# GWLSensorv1.net
KiCad netlist of a schematic drawn in EAGLE
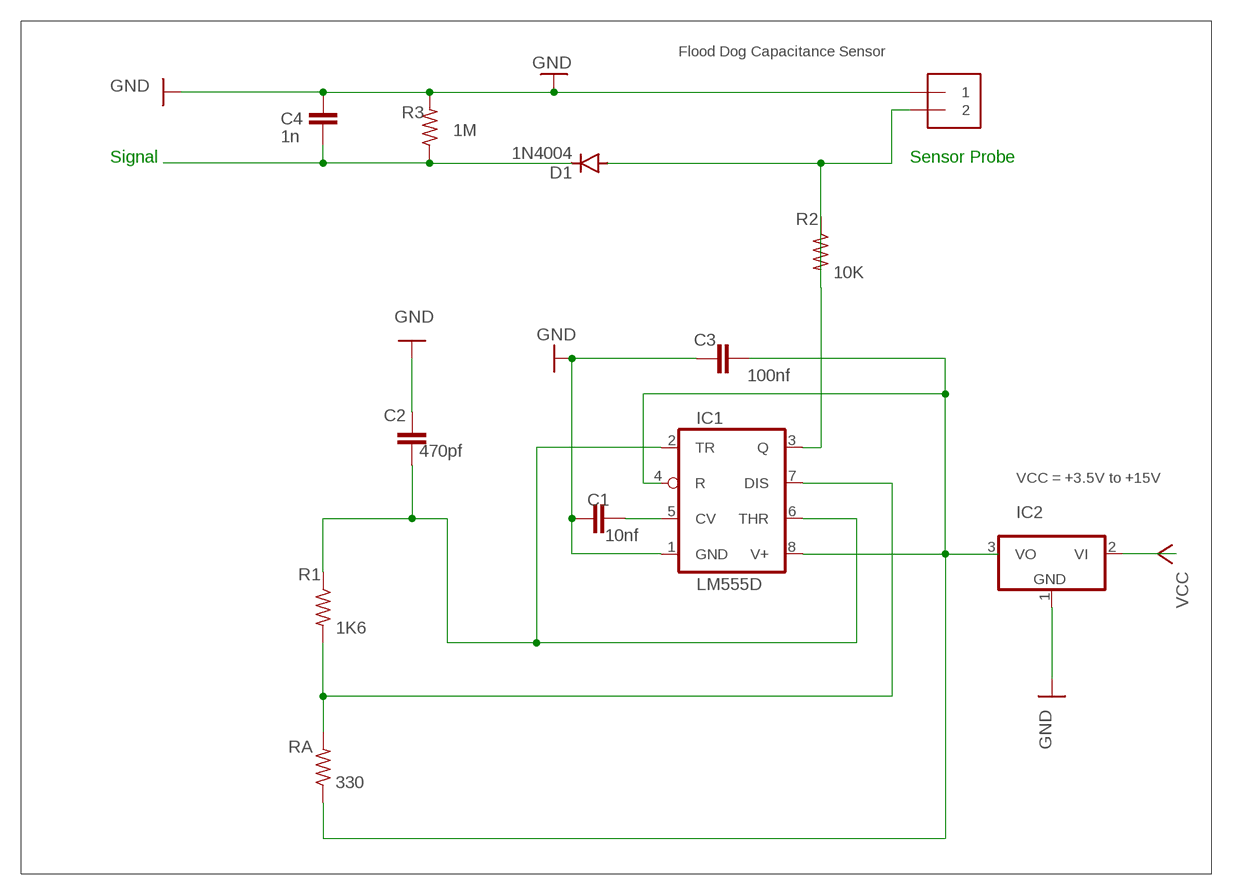
[diagram p0: schematic, sheet 1]

(export (version "E")
  (design (tool "Eeschema 10.0.6"))
  (components
    (comp (ref "C1")
      (value "10nf")
      (footprint "eagle-import:C0805")
      (libsource (lib "eagle-import") (part "C-EUC0805"))
    )
    (comp (ref "C2")
      (value "470pf")
      (footprint "eagle-import:C0805")
      (libsource (lib "eagle-import") (part "C-EUC0805"))
    )
    (comp (ref "C3")
      (value "100nf")
      (footprint "eagle-import:C0805")
      (libsource (lib "eagle-import") (part "C-EUC0805"))
    )
    (comp (ref "C4")
      (value "1n")
      (footprint "eagle-import:C0805")
      (libsource (lib "eagle-import") (part "C-EUC0805"))
    )
    (comp (ref "D1")
      (value "1N4004")
      (footprint "eagle-import:DO41-10")
      (libsource (lib "eagle-import") (part "1N4004"))
    )
    (comp (ref "IC1")
      (value "LM555D")
      (footprint "eagle-import:SO08")
      (libsource (lib "eagle-import") (part "555DLM"))
    )
    (comp (ref "IC2")
      (value "79L15Z")
      (footprint "eagle-import:TO92")
      (libsource (lib "eagle-import") (part "79ZL15"))
    )
    (comp (ref "J1")
      (value "1X2-3.5MM")
      (footprint "eagle-import:1X2-3.5MM")
      (libsource (lib "eagle-import") (part "1X2-3.5MM"))
    )
    (comp (ref "R1")
      (value "1K6")
      (footprint "eagle-import:R0805")
      (libsource (lib "eagle-import") (part "R-US_R0805"))
    )
    (comp (ref "R2")
      (value "10K")
      (footprint "eagle-import:R0805")
      (libsource (lib "eagle-import") (part "R-US_R0805"))
    )
    (comp (ref "R3")
      (value "1M")
      (footprint "eagle-import:R0805")
      (libsource (lib "eagle-import") (part "R-US_R0805"))
    )
    (comp (ref "RA")
      (value "330")
      (footprint "eagle-import:R0805")
      (libsource (lib "eagle-import") (part "R-US_R0805"))
    )
  )
  (nets
    (net (code "1") (name "GND") (class "Default")
      (node (ref "C1") (pin "1") (pinfunction "1_1") (pintype "passive"))
      (node (ref "C2") (pin "1") (pinfunction "1_1") (pintype "passive"))
      (node (ref "C3") (pin "1") (pinfunction "1_1") (pintype "passive"))
      (node (ref "C4") (pin "2") (pinfunction "2_2") (pintype "passive"))
      (node (ref "IC1") (pin "1") (pinfunction "GND_1") (pintype "power_in"))
      (node (ref "IC2") (pin "1") (pinfunction "GND_1") (pintype "passive"))
      (node (ref "J1") (pin "1") (pinfunction "1_1") (pintype "passive"))
      (node (ref "R3") (pin "2") (pinfunction "2_2") (pintype "passive"))
    )
    (net (code "2") (name "Net-(C4-Pad1)") (class "Default")
      (node (ref "C4") (pin "1") (pinfunction "1_1") (pintype "passive"))
      (node (ref "D1") (pin "C") (pinfunction "C_C") (pintype "passive"))
      (node (ref "R3") (pin "1") (pinfunction "1_1") (pintype "passive"))
    )
    (net (code "3") (name "Net-(IC1-CV)") (class "Default")
      (node (ref "C1") (pin "2") (pinfunction "2_2") (pintype "passive"))
      (node (ref "IC1") (pin "5") (pinfunction "CV_5") (pintype "input"))
    )
    (net (code "4") (name "Net-(IC1-DIS)") (class "Default")
      (node (ref "IC1") (pin "7") (pinfunction "DIS_7") (pintype "input"))
      (node (ref "R1") (pin "2") (pinfunction "2_2") (pintype "passive"))
      (node (ref "RA") (pin "2") (pinfunction "2_2") (pintype "passive"))
    )
    (net (code "5") (name "Net-(IC1-Q)") (class "Default")
      (node (ref "D1") (pin "A") (pinfunction "A_A") (pintype "passive"))
      (node (ref "IC1") (pin "3") (pinfunction "Q_3") (pintype "output"))
      (node (ref "J1") (pin "2") (pinfunction "2_2") (pintype "passive"))
      (node (ref "R2") (pin "1") (pinfunction "1_1") (pintype "passive"))
      (node (ref "R2") (pin "2") (pinfunction "2_2") (pintype "passive"))
    )
    (net (code "6") (name "Net-(IC1-R)") (class "Default")
      (node (ref "C3") (pin "2") (pinfunction "2_2") (pintype "passive"))
      (node (ref "IC1") (pin "4") (pinfunction "R_4") (pintype "input"))
      (node (ref "IC1") (pin "8") (pinfunction "V+_8") (pintype "power_in"))
      (node (ref "IC2") (pin "3") (pinfunction "VO_3") (pintype "passive"))
      (node (ref "RA") (pin "1") (pinfunction "1_1") (pintype "passive"))
    )
    (net (code "7") (name "Net-(IC1-THR)") (class "Default")
      (node (ref "C2") (pin "2") (pinfunction "2_2") (pintype "passive"))
      (node (ref "IC1") (pin "2") (pinfunction "TR_2") (pintype "input"))
      (node (ref "IC1") (pin "6") (pinfunction "THR_6") (pintype "input"))
      (node (ref "R1") (pin "1") (pinfunction "1_1") (pintype "passive"))
    )
    (net (code "8") (name "VCC") (class "Default")
      (node (ref "IC2") (pin "2") (pinfunction "VI_2") (pintype "input"))
    )
  )
)
